# Display.net
KiCad netlist of a schematic drawn in Altium Designer
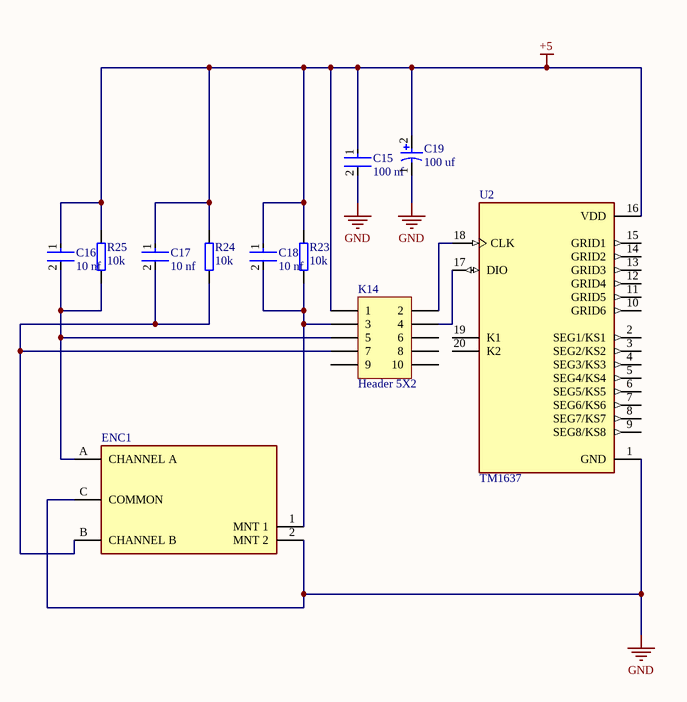
[diagram p0: Display.SchDoc]

(export (version "E")
  (design (tool "Eeschema 10.0.6"))
  (components
    (comp (ref "C15")
      (value "100 nf")
      (footprint "CC_0805_L")
      (fields
        (field (name "MANUFACTURER") "KEMET")
        (field (name "OCTOPART") "https://octopart.com/c0805c224k5ractu-kemet-144670")
        (field (name "MANUFACTURER PART NUMBER") "C0805C224K5RACTU")
      )
      (libsource (lib "Soldeerstation_Final") (part "Capacitor_Ceramic"))
    )
    (comp (ref "C16")
      (value "10 nf")
      (footprint "CC_0805_L")
      (fields
        (field (name "MANUFACTURER") "KEMET")
        (field (name "OCTOPART") "https://octopart.com/c0805c224k5ractu-kemet-144670")
        (field (name "MANUFACTURER PART NUMBER") "C0805C224K5RACTU")
      )
      (libsource (lib "Soldeerstation_Final") (part "Capacitor_Ceramic"))
    )
    (comp (ref "C17")
      (value "10 nf")
      (footprint "CC_0805_L")
      (fields
        (field (name "MANUFACTURER") "KEMET")
        (field (name "OCTOPART") "https://octopart.com/c0805c224k5ractu-kemet-144670")
        (field (name "MANUFACTURER PART NUMBER") "C0805C224K5RACTU")
      )
      (libsource (lib "Soldeerstation_Final") (part "Capacitor_Ceramic"))
    )
    (comp (ref "C18")
      (value "10 nf")
      (footprint "CC_0805_L")
      (fields
        (field (name "MANUFACTURER") "KEMET")
        (field (name "OCTOPART") "https://octopart.com/c0805c224k5ractu-kemet-144670")
        (field (name "MANUFACTURER PART NUMBER") "C0805C224K5RACTU")
      )
      (libsource (lib "Soldeerstation_Final") (part "Capacitor_Ceramic"))
    )
    (comp (ref "C19")
      (value "100 uf")
      (footprint "CE_D8_L10")
      (fields (field (name "MANUFACTURER") "Panasonic"))
      (libsource (lib "Soldeerstation_Final") (part "Capacitor_Electrolytic"))
    )
    (comp (ref "ENC1")
      (value "~")
      (footprint "PEC11R4225FN0024")
      (fields
        (field (name "MANUFACTURER PART NUMBER") "PEC11R-4015F-N0024")
        (field (name "MANUFACTURER") "Bourns")
        (field (name "OCTOPART") "https://octopart.com/pec11r-4015f-n0024-bourns-26648251")
      )
      (libsource (lib "Soldeerstation_Final") (part "ROTARY_ENCODER"))
    )
    (comp (ref "K14")
      (value "Header 5X2")
      (footprint "HDR2X5")
      (description "Header, 5-Pin, Dual row")
      (fields (field (name "PUBLISHER") "Altium Limited"))
      (libsource (lib "Miscellaneous Connectors") (part "Header 5X2"))
    )
    (comp (ref "R23")
      (value "10k")
      (footprint "0805_M")
      (fields (field (name "MANUFACTURER") "Vishay Dale") (field (name "PART NUMBER") "CRCW08050000Z0EA"))
      (libsource (lib "Soldeerstation_Final") (part "Resistor"))
    )
    (comp (ref "R24")
      (value "10k")
      (footprint "0805_M")
      (fields (field (name "MANUFACTURER") "Vishay Dale") (field (name "PART NUMBER") "CRCW08050000Z0EA"))
      (libsource (lib "Soldeerstation_Final") (part "Resistor"))
    )
    (comp (ref "R25")
      (value "10k")
      (footprint "0805_M")
      (fields (field (name "MANUFACTURER") "Vishay Dale") (field (name "PART NUMBER") "CRCW08050000Z0EA"))
      (libsource (lib "Soldeerstation_Final") (part "Resistor"))
    )
    (comp (ref "U2")
      (value "TM1637")
      (footprint "SOP_20_M")
      (description "LED Drive Control Special Circuit")
      (fields (field (name "MF") "Titan Micro Electronics"))
      (libsource (lib "Soldeerstation_Final") (part "TM1637"))
    )
  )
  (nets
    (net (code "1") (name "+5") (class "Default")
      (node (ref "C15") (pin "1") (pinfunction "1_1") (pintype "passive"))
      (node (ref "C16") (pin "1") (pinfunction "1_1") (pintype "passive"))
      (node (ref "C17") (pin "1") (pinfunction "1_1") (pintype "passive"))
      (node (ref "C18") (pin "1") (pinfunction "1_1") (pintype "passive"))
      (node (ref "C19") (pin "2") (pinfunction "2_2") (pintype "passive"))
      (node (ref "K14") (pin "1") (pinfunction "1_1") (pintype "passive"))
      (node (ref "R23") (pin "2") (pinfunction "2_2") (pintype "passive"))
      (node (ref "R24") (pin "2") (pinfunction "2_2") (pintype "passive"))
      (node (ref "R25") (pin "2") (pinfunction "2_2") (pintype "passive"))
      (node (ref "U2") (pin "16") (pinfunction "VDD_16") (pintype "power_in"))
    )
    (net (code "2") (name "GND") (class "Default")
      (node (ref "C15") (pin "2") (pinfunction "2_2") (pintype "passive"))
      (node (ref "C19") (pin "1") (pinfunction "1_1") (pintype "passive"))
      (node (ref "ENC1") (pin "2") (pinfunction "MNT_2_2") (pintype "passive"))
      (node (ref "ENC1") (pin "C") (pinfunction "COMMON_C") (pintype "passive"))
      (node (ref "U2") (pin "1") (pinfunction "GND_1") (pintype "power_in"))
    )
    (net (code "3") (name "Net-(ENC1-CHANNEL_A)") (class "Default")
      (node (ref "C16") (pin "2") (pinfunction "2_2") (pintype "passive"))
      (node (ref "ENC1") (pin "A") (pinfunction "CHANNEL_A_A") (pintype "passive"))
      (node (ref "K14") (pin "5") (pinfunction "5_5") (pintype "passive"))
      (node (ref "R25") (pin "1") (pinfunction "1_1") (pintype "passive"))
    )
    (net (code "4") (name "Net-(ENC1-CHANNEL_B)") (class "Default")
      (node (ref "C17") (pin "2") (pinfunction "2_2") (pintype "passive"))
      (node (ref "ENC1") (pin "B") (pinfunction "CHANNEL_B_B") (pintype "passive"))
      (node (ref "K14") (pin "7") (pinfunction "7_7") (pintype "passive"))
      (node (ref "R24") (pin "1") (pinfunction "1_1") (pintype "passive"))
    )
    (net (code "5") (name "Net-(ENC1-MNT_1)") (class "Default")
      (node (ref "C18") (pin "2") (pinfunction "2_2") (pintype "passive"))
      (node (ref "ENC1") (pin "1") (pinfunction "MNT_1_1") (pintype "passive"))
      (node (ref "K14") (pin "3") (pinfunction "3_3") (pintype "passive"))
      (node (ref "R23") (pin "1") (pinfunction "1_1") (pintype "passive"))
    )
    (net (code "6") (name "Net-(U2-CLK)") (class "Default")
      (node (ref "K14") (pin "2") (pinfunction "2_2") (pintype "passive"))
      (node (ref "U2") (pin "18") (pinfunction "CLK_18") (pintype "input"))
    )
    (net (code "7") (name "Net-(U2-DIO)") (class "Default")
      (node (ref "K14") (pin "4") (pinfunction "4_4") (pintype "passive"))
      (node (ref "U2") (pin "17") (pinfunction "DIO_17") (pintype "bidirectional"))
    )
    (net (code "8") (name "unconnected-(K14-Pad6)") (class "Default")
      (node (ref "K14") (pin "6") (pinfunction "6_6") (pintype "passive"))
    )
    (net (code "9") (name "unconnected-(K14-Pad8)") (class "Default")
      (node (ref "K14") (pin "8") (pinfunction "8_8") (pintype "passive"))
    )
    (net (code "10") (name "unconnected-(K14-Pad9)") (class "Default")
      (node (ref "K14") (pin "9") (pinfunction "9_9") (pintype "passive"))
    )
    (net (code "11") (name "unconnected-(K14-Pad10)") (class "Default")
      (node (ref "K14") (pin "10") (pinfunction "10_10") (pintype "passive"))
    )
    (net (code "12") (name "unconnected-(U2-GRID1-Pad15)") (class "Default")
      (node (ref "U2") (pin "15") (pinfunction "GRID1_15") (pintype "output"))
    )
    (net (code "13") (name "unconnected-(U2-GRID2-Pad14)") (class "Default")
      (node (ref "U2") (pin "14") (pinfunction "GRID2_14") (pintype "output"))
    )
    (net (code "14") (name "unconnected-(U2-GRID3-Pad13)") (class "Default")
      (node (ref "U2") (pin "13") (pinfunction "GRID3_13") (pintype "output"))
    )
    (net (code "15") (name "unconnected-(U2-GRID4-Pad12)") (class "Default")
      (node (ref "U2") (pin "12") (pinfunction "GRID4_12") (pintype "output"))
    )
    (net (code "16") (name "unconnected-(U2-GRID5-Pad11)") (class "Default")
      (node (ref "U2") (pin "11") (pinfunction "GRID5_11") (pintype "output"))
    )
    (net (code "17") (name "unconnected-(U2-GRID6-Pad10)") (class "Default")
      (node (ref "U2") (pin "10") (pinfunction "GRID6_10") (pintype "output"))
    )
    (net (code "18") (name "unconnected-(U2-K1-Pad19)") (class "Default")
      (node (ref "U2") (pin "19") (pinfunction "K1_19") (pintype "passive"))
    )
    (net (code "19") (name "unconnected-(U2-K2-Pad20)") (class "Default")
      (node (ref "U2") (pin "20") (pinfunction "K2_20") (pintype "passive"))
    )
    (net (code "20") (name "unconnected-(U2-SEG1{slash}KS1-Pad2)") (class "Default")
      (node (ref "U2") (pin "2") (pinfunction "SEG1/KS1_2") (pintype "output"))
    )
    (net (code "21") (name "unconnected-(U2-SEG2{slash}KS2-Pad3)") (class "Default")
      (node (ref "U2") (pin "3") (pinfunction "SEG2/KS2_3") (pintype "output"))
    )
    (net (code "22") (name "unconnected-(U2-SEG3{slash}KS3-Pad4)") (class "Default")
      (node (ref "U2") (pin "4") (pinfunction "SEG3/KS3_4") (pintype "output"))
    )
    (net (code "23") (name "unconnected-(U2-SEG4{slash}KS4-Pad5)") (class "Default")
      (node (ref "U2") (pin "5") (pinfunction "SEG4/KS4_5") (pintype "output"))
    )
    (net (code "24") (name "unconnected-(U2-SEG5{slash}KS5-Pad6)") (class "Default")
      (node (ref "U2") (pin "6") (pinfunction "SEG5/KS5_6") (pintype "output"))
    )
    (net (code "25") (name "unconnected-(U2-SEG6{slash}KS6-Pad7)") (class "Default")
      (node (ref "U2") (pin "7") (pinfunction "SEG6/KS6_7") (pintype "output"))
    )
    (net (code "26") (name "unconnected-(U2-SEG7{slash}KS7-Pad8)") (class "Default")
      (node (ref "U2") (pin "8") (pinfunction "SEG7/KS7_8") (pintype "output"))
    )
    (net (code "27") (name "unconnected-(U2-SEG8{slash}KS8-Pad9)") (class "Default")
      (node (ref "U2") (pin "9") (pinfunction "SEG8/KS8_9") (pintype "output"))
    )
  )
)
